# USBserial.net
KiCad netlist of a schematic drawn in Altium Designer
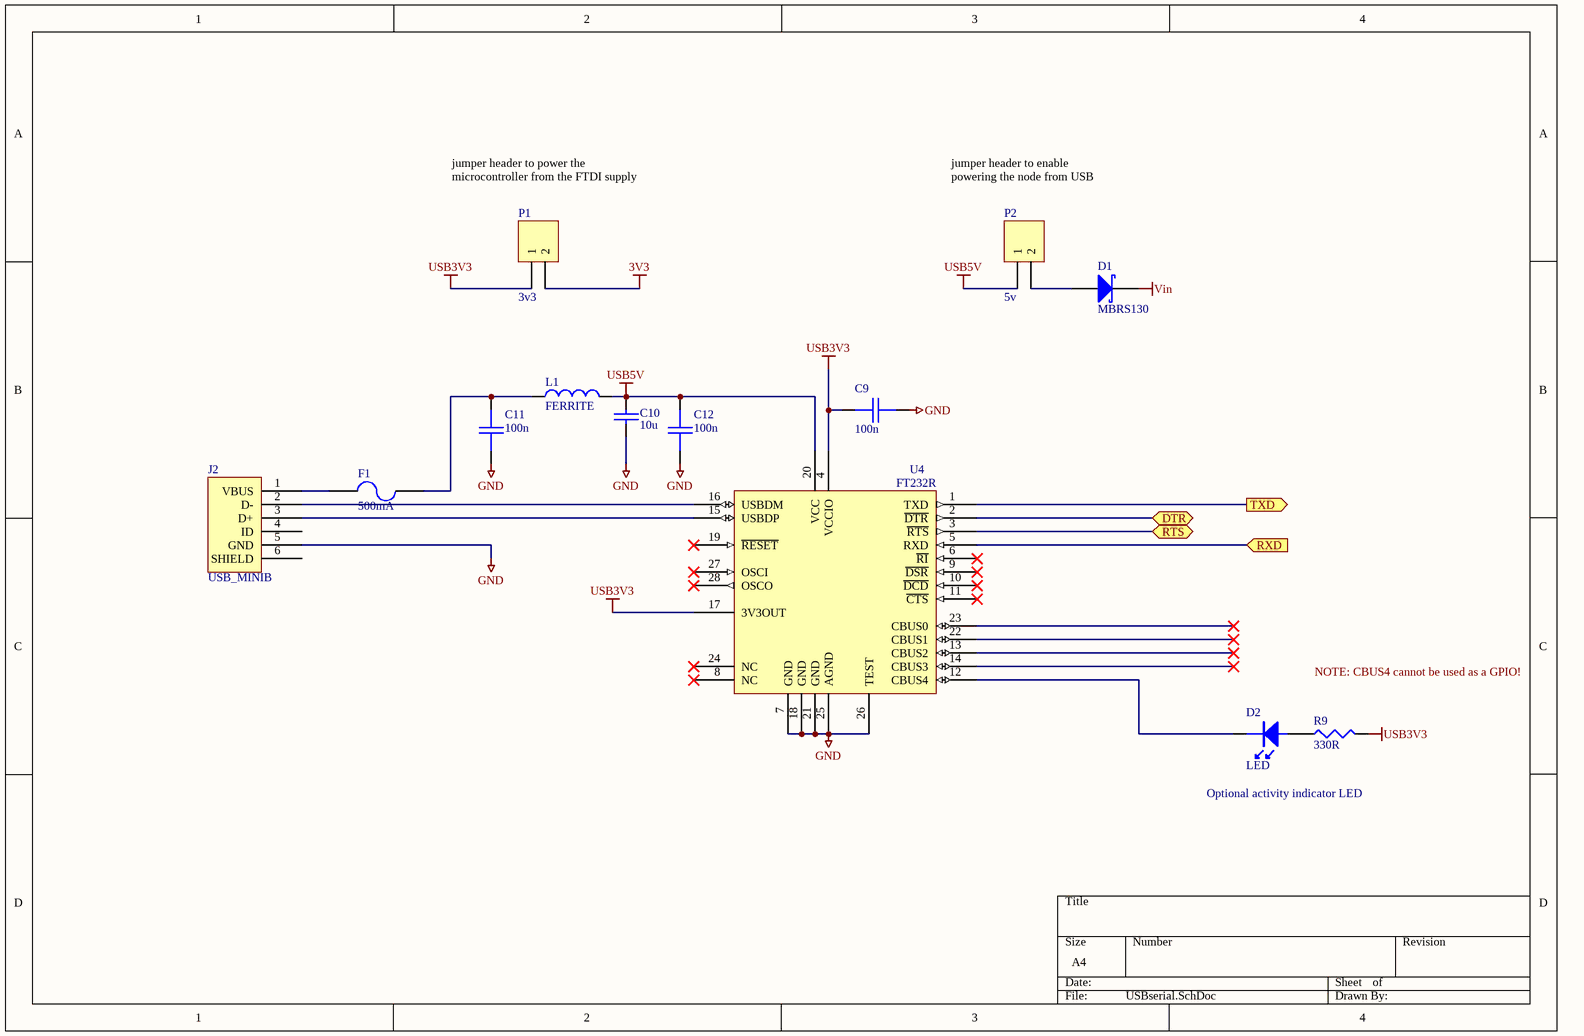
[diagram p0: USBserial.SchDoc]

(export (version "E")
  (design (tool "Eeschema 10.0.6"))
  (components
    (comp (ref "C9")
      (value "100n")
      (footprint "0603")
      (description "Capacitor")
      (libsource (lib "RCLDQ") (part "CAP"))
    )
    (comp (ref "C10")
      (value "10u")
      (footprint "0805")
      (description "Capacitor")
      (libsource (lib "*") (part "CAP"))
    )
    (comp (ref "C11")
      (value "100n")
      (footprint "0603")
      (description "Capacitor")
      (libsource (lib "RCLDQ") (part "CAP"))
    )
    (comp (ref "C12")
      (value "100n")
      (footprint "0603")
      (description "Capacitor")
      (libsource (lib "RCLDQ") (part "CAP"))
    )
    (comp (ref "D1")
      (value "MBRS130")
      (footprint "SMB")
      (description "Schottky Diode")
      (libsource (lib "RCLDQ") (part "D SCHOTTKY"))
    )
    (comp (ref "D2") (value "LED") (footprint "0805LED") (libsource (lib "RCLDQ") (part "LED")))
    (comp (ref "F1")
      (value "500mA")
      (footprint "1812")
      (description "Fuse")
      (libsource (lib "*") (part "FUSE2"))
    )
    (comp (ref "J2")
      (value "USB_MINIB")
      (footprint "USB_MINIB_UX60SC")
      (description "USB Mini B Connector")
      (libsource (lib "sion") (part "USB_miniB_SMT"))
    )
    (comp (ref "L1")
      (value "FERRITE")
      (footprint "0805")
      (description "Inductor")
      (fields (field (name "MANUFACTURER") "Generic Components"))
      (libsource (lib "RCLDQ") (part "INDUCTOR"))
    )
    (comp (ref "P1")
      (value "3v3")
      (footprint "HDR1X2")
      (description "Header, 2-Pin")
      (fields (field (name "PUBLISHER") "Altium Limited"))
      (libsource (lib "Miscellaneous Connectors") (part "Header 2"))
    )
    (comp (ref "P2")
      (value "5v")
      (footprint "HDR1X2")
      (description "Header, 2-Pin")
      (fields (field (name "PUBLISHER") "Altium Limited"))
      (libsource (lib "Miscellaneous Connectors") (part "Header 2"))
    )
    (comp (ref "R9")
      (value "330R")
      (footprint "0603")
      (description "Resistor")
      (libsource (lib "RCLDQ") (part "RES1"))
    )
    (comp (ref "U4")
      (value "FT232R")
      (footprint "SSOP28w")
      (libsource (lib "MiscellaneousIC") (part "FT232R"))
    )
  )
  (nets
    (net (code "1") (name "/DTR") (class "Default")
      (node (ref "U4") (pin "2") (pinfunction "~{DTR}_2") (pintype "output"))
    )
    (net (code "2") (name "/RTS") (class "Default")
      (node (ref "U4") (pin "3") (pinfunction "~{RTS}_3") (pintype "output"))
    )
    (net (code "3") (name "/RXD") (class "Default")
      (node (ref "U4") (pin "5") (pinfunction "RXD_5") (pintype "input"))
    )
    (net (code "4") (name "/TXD") (class "Default")
      (node (ref "U4") (pin "1") (pinfunction "TXD_1") (pintype "output"))
    )
    (net (code "5") (name "3V3") (class "Default")
      (node (ref "P1") (pin "2") (pinfunction "2_2") (pintype "passive"))
    )
    (net (code "6") (name "GND") (class "Default")
      (node (ref "C10") (pin "1") (pinfunction "1_1") (pintype "passive"))
      (node (ref "C11") (pin "2") (pinfunction "2_2") (pintype "passive"))
      (node (ref "C12") (pin "2") (pinfunction "2_2") (pintype "passive"))
      (node (ref "C9") (pin "2") (pinfunction "2_2") (pintype "passive"))
      (node (ref "J2") (pin "5") (pinfunction "GND_5") (pintype "passive"))
      (node (ref "U4") (pin "18") (pinfunction "GND_18") (pintype "power_in"))
      (node (ref "U4") (pin "21") (pinfunction "GND_21") (pintype "power_in"))
      (node (ref "U4") (pin "25") (pinfunction "AGND_25") (pintype "power_in"))
      (node (ref "U4") (pin "26") (pinfunction "TEST_26") (pintype "passive"))
      (node (ref "U4") (pin "7") (pinfunction "GND_7") (pintype "power_in"))
    )
    (net (code "7") (name "Net-(C11-Pad1)") (class "Default")
      (node (ref "C11") (pin "1") (pinfunction "1_1") (pintype "passive"))
      (node (ref "F1") (pin "2") (pinfunction "2_2") (pintype "passive"))
      (node (ref "L1") (pin "1") (pinfunction "1_1") (pintype "passive"))
    )
    (net (code "8") (name "Net-(D1-PadA)") (class "Default")
      (node (ref "D1") (pin "A") (pinfunction "A_A") (pintype "passive"))
      (node (ref "P2") (pin "2") (pinfunction "2_2") (pintype "passive"))
    )
    (net (code "9") (name "Net-(D2-PadA)") (class "Default")
      (node (ref "D2") (pin "A") (pinfunction "A_A") (pintype "passive"))
      (node (ref "R9") (pin "1") (pinfunction "1_1") (pintype "passive"))
    )
    (net (code "10") (name "Net-(J2-D+)") (class "Default")
      (node (ref "J2") (pin "3") (pinfunction "D+_3") (pintype "passive"))
      (node (ref "U4") (pin "15") (pinfunction "USBDP_15") (pintype "bidirectional"))
    )
    (net (code "11") (name "Net-(J2-D-)") (class "Default")
      (node (ref "J2") (pin "2") (pinfunction "D-_2") (pintype "passive"))
      (node (ref "U4") (pin "16") (pinfunction "USBDM_16") (pintype "bidirectional"))
    )
    (net (code "12") (name "Net-(J2-VBUS)") (class "Default")
      (node (ref "F1") (pin "1") (pinfunction "1_1") (pintype "passive"))
      (node (ref "J2") (pin "1") (pinfunction "VBUS_1") (pintype "passive"))
    )
    (net (code "13") (name "Net-(U4-CBUS4)") (class "Default")
      (node (ref "D2") (pin "K") (pinfunction "K_K") (pintype "passive"))
      (node (ref "U4") (pin "12") (pinfunction "CBUS4_12") (pintype "bidirectional"))
    )
    (net (code "14") (name "USB3V3") (class "Default")
      (node (ref "C9") (pin "1") (pinfunction "1_1") (pintype "passive"))
      (node (ref "P1") (pin "1") (pinfunction "1_1") (pintype "passive"))
      (node (ref "R9") (pin "2") (pinfunction "2_2") (pintype "passive"))
      (node (ref "U4") (pin "17") (pinfunction "3V3OUT_17") (pintype "power_in"))
      (node (ref "U4") (pin "4") (pinfunction "VCCIO_4") (pintype "power_in"))
    )
    (net (code "15") (name "USB5V") (class "Default")
      (node (ref "C10") (pin "2") (pinfunction "2_2") (pintype "passive"))
      (node (ref "C12") (pin "1") (pinfunction "1_1") (pintype "passive"))
      (node (ref "L1") (pin "2") (pinfunction "2_2") (pintype "passive"))
      (node (ref "P2") (pin "1") (pinfunction "1_1") (pintype "passive"))
      (node (ref "U4") (pin "20") (pinfunction "VCC_20") (pintype "power_in"))
    )
    (net (code "16") (name "Vin") (class "Default")
      (node (ref "D1") (pin "K") (pinfunction "K_K") (pintype "passive"))
    )
    (net (code "17") (name "unconnected-(J2-ID-Pad4)") (class "Default")
      (node (ref "J2") (pin "4") (pinfunction "ID_4") (pintype "passive"))
    )
    (net (code "18") (name "unconnected-(J2-SHIELD-Pad6)") (class "Default")
      (node (ref "J2") (pin "6") (pinfunction "SHIELD_6") (pintype "passive"))
    )
    (net (code "19") (name "unconnected-(U4-CBUS0-Pad23)") (class "Default")
      (node (ref "U4") (pin "23") (pinfunction "CBUS0_23") (pintype "bidirectional+no_connect"))
    )
    (net (code "20") (name "unconnected-(U4-CBUS1-Pad22)") (class "Default")
      (node (ref "U4") (pin "22") (pinfunction "CBUS1_22") (pintype "bidirectional+no_connect"))
    )
    (net (code "21") (name "unconnected-(U4-CBUS2-Pad13)") (class "Default")
      (node (ref "U4") (pin "13") (pinfunction "CBUS2_13") (pintype "bidirectional+no_connect"))
    )
    (net (code "22") (name "unconnected-(U4-CBUS3-Pad14)") (class "Default")
      (node (ref "U4") (pin "14") (pinfunction "CBUS3_14") (pintype "bidirectional+no_connect"))
    )
    (net (code "23") (name "unconnected-(U4-NC-Pad8)") (class "Default")
      (node (ref "U4") (pin "8") (pinfunction "NC_8") (pintype "passive+no_connect"))
    )
    (net (code "24") (name "unconnected-(U4-NC-Pad24)") (class "Default")
      (node (ref "U4") (pin "24") (pinfunction "NC_24") (pintype "passive+no_connect"))
    )
    (net (code "25") (name "unconnected-(U4-OSCI-Pad27)") (class "Default")
      (node (ref "U4") (pin "27") (pinfunction "OSCI_27") (pintype "input+no_connect"))
    )
    (net (code "26") (name "unconnected-(U4-OSCO-Pad28)") (class "Default")
      (node (ref "U4") (pin "28") (pinfunction "OSCO_28") (pintype "output+no_connect"))
    )
    (net (code "27") (name "unconnected-(U4-~{CTS}-Pad11)") (class "Default")
      (node (ref "U4") (pin "11") (pinfunction "~{CTS}_11") (pintype "input+no_connect"))
    )
    (net (code "28") (name "unconnected-(U4-~{DCD}-Pad10)") (class "Default")
      (node (ref "U4") (pin "10") (pinfunction "~{DCD}_10") (pintype "input+no_connect"))
    )
    (net (code "29") (name "unconnected-(U4-~{DSR}-Pad9)") (class "Default")
      (node (ref "U4") (pin "9") (pinfunction "~{DSR}_9") (pintype "input+no_connect"))
    )
    (net (code "30") (name "unconnected-(U4-~{RESET}-Pad19)") (class "Default")
      (node (ref "U4") (pin "19") (pinfunction "~{RESET}_19") (pintype "input+no_connect"))
    )
    (net (code "31") (name "unconnected-(U4-~{RI}-Pad6)") (class "Default")
      (node (ref "U4") (pin "6") (pinfunction "~{RI}_6") (pintype "input+no_connect"))
    )
  )
)
